# RemoteMotion.net
KiCad netlist of a schematic drawn in EAGLE
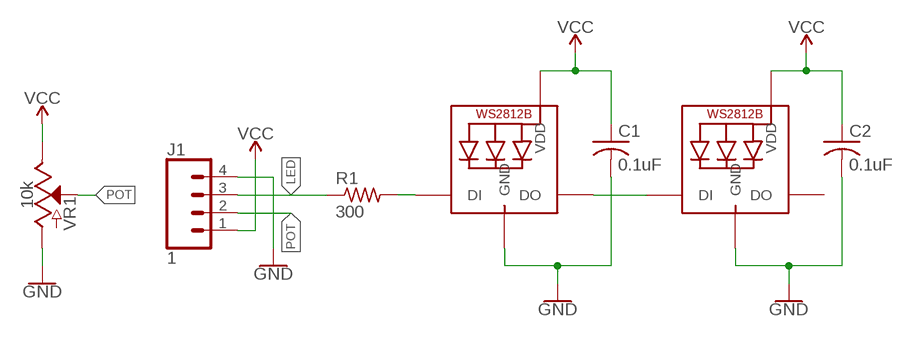
[diagram p0: schematic, sheet 1]

(export (version "E")
  (design (tool "Eeschema 10.0.6"))
  (components
    (comp (ref "C1")
      (value "0.1uF")
      (footprint "eagle-import:C0805")
      (libsource (lib "eagle-import") (part "C-USC0805"))
    )
    (comp (ref "C2")
      (value "0.1uF")
      (footprint "eagle-import:C0805")
      (libsource (lib "eagle-import") (part "C-USC0805"))
    )
    (comp (ref "J1")
      (value "1")
      (footprint "eagle-import:JST-4-PTH")
      (libsource (lib "eagle-import") (part "CONN_04JST-PTH"))
    )
    (comp (ref "LED1")
      (value "WS2812B5050")
      (footprint "eagle-import:WS2812B")
      (libsource (lib "eagle-import") (part "WS2812B5050"))
    )
    (comp (ref "LED2")
      (value "WS2812B5050")
      (footprint "eagle-import:WS2812B")
      (libsource (lib "eagle-import") (part "WS2812B5050"))
    )
    (comp (ref "R1")
      (value "300")
      (footprint "eagle-import:R0805")
      (libsource (lib "eagle-import") (part "R-US_R0805"))
    )
    (comp (ref "VR1")
      (value "10k")
      (footprint "eagle-import:SLIDER-XLARGE")
      (libsource (lib "eagle-import") (part "POTENTIOMETER_SLIDE-60MM-1/2W-20%"))
    )
  )
  (nets
    (net (code "1") (name "GND") (class "Default")
      (node (ref "C1") (pin "2") (pinfunction "2_2") (pintype "passive"))
      (node (ref "C2") (pin "2") (pinfunction "2_2") (pintype "passive"))
      (node (ref "J1") (pin "4") (pinfunction "4_4") (pintype "passive"))
      (node (ref "LED1") (pin "3-GND") (pinfunction "GND_3-GND") (pintype "power_in"))
      (node (ref "LED2") (pin "3-GND") (pinfunction "GND_3-GND") (pintype "power_in"))
      (node (ref "VR1") (pin "3") (pinfunction "A_3") (pintype "passive"))
    )
    (net (code "2") (name "LED") (class "Default")
      (node (ref "J1") (pin "3") (pinfunction "3_3") (pintype "passive"))
      (node (ref "R1") (pin "1") (pinfunction "1_1") (pintype "passive"))
    )
    (net (code "3") (name "Net-(LED1-DI)") (class "Default")
      (node (ref "LED1") (pin "4-DIN") (pinfunction "DI_4-DIN") (pintype "input"))
      (node (ref "R1") (pin "2") (pinfunction "2_2") (pintype "passive"))
    )
    (net (code "4") (name "Net-(LED1-DO)") (class "Default")
      (node (ref "LED1") (pin "2-DOUT") (pinfunction "DO_2-DOUT") (pintype "output"))
      (node (ref "LED2") (pin "4-DIN") (pinfunction "DI_4-DIN") (pintype "input"))
    )
    (net (code "5") (name "POT") (class "Default")
      (node (ref "J1") (pin "2") (pinfunction "2_2") (pintype "passive"))
      (node (ref "VR1") (pin "2A") (pinfunction "S_2A") (pintype "passive"))
    )
    (net (code "6") (name "VCC") (class "Default")
      (node (ref "C1") (pin "1") (pinfunction "1_1") (pintype "passive"))
      (node (ref "C2") (pin "1") (pinfunction "1_1") (pintype "passive"))
      (node (ref "J1") (pin "1") (pinfunction "1_1") (pintype "passive"))
      (node (ref "LED1") (pin "1-VDD") (pinfunction "VDD_1-VDD") (pintype "power_in"))
      (node (ref "LED2") (pin "1-VDD") (pinfunction "VDD_1-VDD") (pintype "power_in"))
      (node (ref "VR1") (pin "1") (pinfunction "E_1") (pintype "passive"))
    )
    (net (code "7") (name "unconnected-(LED2-DO-Pad2-DOUT)") (class "Default")
      (node (ref "LED2") (pin "2-DOUT") (pinfunction "DO_2-DOUT") (pintype "output"))
    )
  )
)
